# 06_iMX_8X_CAN.net
KiCad netlist of a schematic drawn in Altium Designer
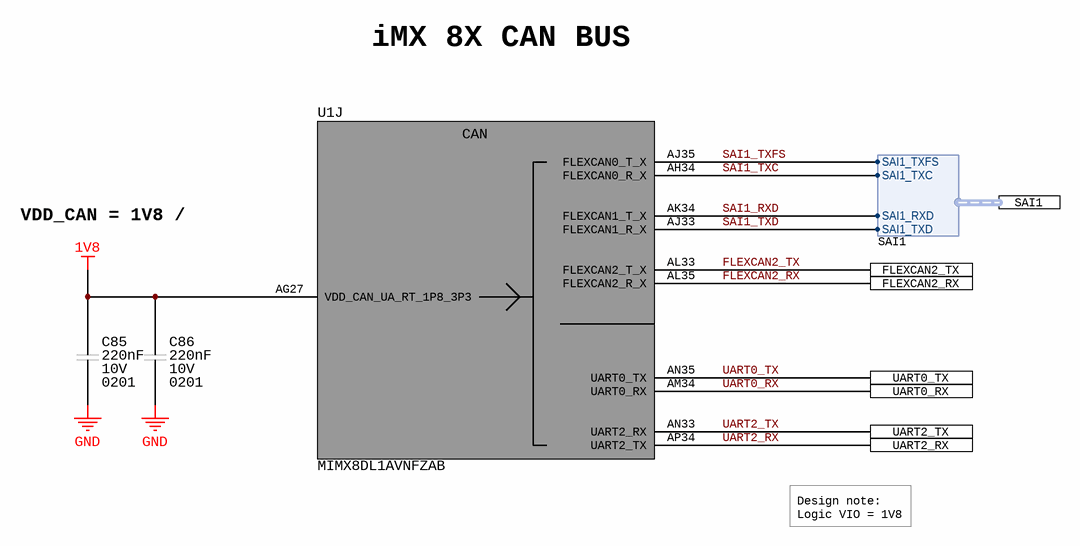
[diagram p0: 06_iMX 8X_CAN.SchDoc]

(export (version "E")
  (design (tool "Eeschema 10.0.6"))
  (components
    (comp (ref "C85")
      (value "LMK063BJ224MP-F")
      (footprint "CAP_0201_CAPC0603X03N")
      (description "Multilayer Ceramic Capacitors (High dielectric type), 10V, 0.22 uF, ± 20 %, 0201, X5R, RoHS")
      (fields
        (field (name "MANUFACTURER") "Taiyo Yuden")
        (field (name "TOLERANCE") "20%")
        (field (name "VOLTAGE RATING (DC)") "10V")
        (field (name "CAPACITANCE") "220nF")
        (field (name "CASE/PACKAGE") "0201")
      )
      (libsource (lib "Electronic Devices_LIB") (part "CAP_0.22UF_10V_X5R_0201"))
    )
    (comp (ref "C86")
      (value "LMK063BJ224MP-F")
      (footprint "CAP_0201_CAPC0603X03N")
      (description "Multilayer Ceramic Capacitors (High dielectric type), 10V, 0.22 uF, ± 20 %, 0201, X5R, RoHS")
      (fields
        (field (name "MANUFACTURER") "Taiyo Yuden")
        (field (name "TOLERANCE") "20%")
        (field (name "VOLTAGE RATING (DC)") "10V")
        (field (name "CAPACITANCE") "220nF")
        (field (name "CASE/PACKAGE") "0201")
      )
      (libsource (lib "Electronic Devices_LIB") (part "CAP_0.22UF_10V_X5R_0201"))
    )
    (comp (ref "U1")
      (value "MIMX8DL1AVNFZAB")
      (footprint "MIMX8DL1AVNFZAB")
      (description "I.MX8 Dxl 15SQ / Tray Rohs Compliant: Yes")
      (fields (field (name "MANUFACTURER") "NXP Semiconductors"))
      (libsource (lib "Electronic Devices_LIB") (part "IC_MPU_ARM_1.2GHz_MIMX8DL1AVNFZAB"))
    )
  )
  (nets
    (net (code "2") (name "/FLEXCAN2_RX") (class "Default")
      (node (ref "U1") (pin "AL35") (pinfunction "FLEXCAN2_R_X_AL35") (pintype "passive"))
    )
    (net (code "3") (name "/FLEXCAN2_TX") (class "Default")
      (node (ref "U1") (pin "AL33") (pinfunction "FLEXCAN2_T_X_AL33") (pintype "passive"))
    )
    (net (code "4") (name "/SAI1_RXD") (class "Default")
      (node (ref "U1") (pin "AK34") (pinfunction "FLEXCAN1_T_X_AK34") (pintype "passive"))
    )
    (net (code "5") (name "/SAI1_TXC") (class "Default")
      (node (ref "U1") (pin "AH34") (pinfunction "FLEXCAN0_R_X_AH34") (pintype "passive"))
    )
    (net (code "6") (name "/SAI1_TXD") (class "Default")
      (node (ref "U1") (pin "AJ33") (pinfunction "FLEXCAN1_R_X_AJ33") (pintype "passive"))
    )
    (net (code "7") (name "/SAI1_TXFS") (class "Default")
      (node (ref "U1") (pin "AJ35") (pinfunction "FLEXCAN0_T_X_AJ35") (pintype "passive"))
    )
    (net (code "8") (name "/UART0_RX") (class "Default")
      (node (ref "U1") (pin "AM34") (pinfunction "UART0_RX_AM34") (pintype "passive"))
    )
    (net (code "9") (name "/UART0_TX") (class "Default")
      (node (ref "U1") (pin "AN35") (pinfunction "UART0_TX_AN35") (pintype "passive"))
    )
    (net (code "10") (name "/UART2_RX") (class "Default")
      (node (ref "U1") (pin "AP34") (pinfunction "UART2_TX_AP34") (pintype "passive"))
    )
    (net (code "11") (name "/UART2_TX") (class "Default")
      (node (ref "U1") (pin "AN33") (pinfunction "UART2_RX_AN33") (pintype "passive"))
    )
    (net (code "13") (name "1V8") (class "Default")
      (node (ref "C85") (pin "2") (pinfunction "2_2") (pintype "passive"))
      (node (ref "C86") (pin "2") (pinfunction "2_2") (pintype "passive"))
      (node (ref "U1") (pin "AG27") (pinfunction "VDD_CAN_UA_RT_1P8_3P3_AG27") (pintype "passive"))
    )
    (net (code "14") (name "GND") (class "Default")
      (node (ref "C85") (pin "1") (pinfunction "1_1") (pintype "passive"))
      (node (ref "C86") (pin "1") (pinfunction "1_1") (pintype "passive"))
    )
  )
)
